# Extend.net
KiCad netlist of a schematic drawn in Altium Designer
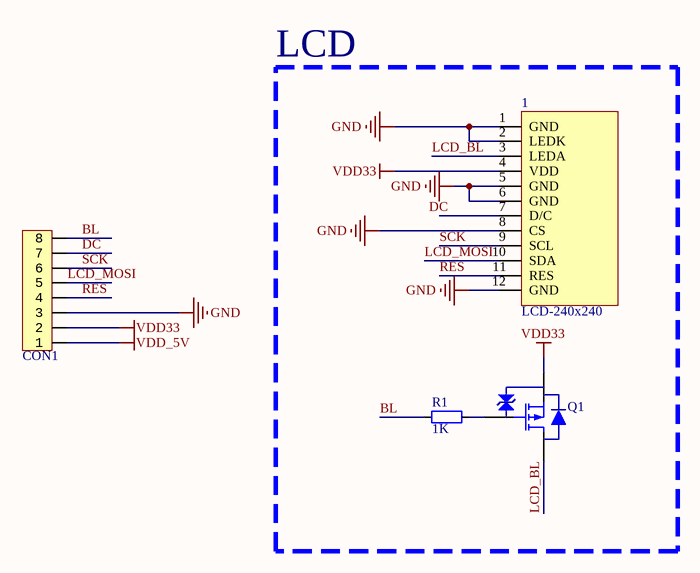
[diagram p0: Extend.SchDoc]

(export (version "E")
  (design (tool "Eeschema 10.0.6"))
  (components
    (comp (ref "1")
      (value "LCD-240x240")
      (footprint "LCD-240x240-NoHole")
      (description "显示屏")
      (libsource (lib "ExtendBoard") (part "LCD-240x240"))
    )
    (comp (ref "CON1")
      (value "FFC_0.5_8")
      (footprint "FFC_0.5_8")
      (description "FFC")
      (libsource (lib "ExtendBoard") (part "FFC_0.5_8"))
    )
    (comp (ref "Q1")
      (value "AO3415A")
      (footprint "SOT23-3")
      (description "MOSFET")
      (fields (field (name "PUBLISHER") "Altium Limited"))
      (libsource (lib "ExtendBoard") (part "AO3415A"))
    )
    (comp (ref "R1")
      (value "1K")
      (footprint "RES_0402")
      (description "Resistor")
      (libsource (lib "ExtendBoard") (part "电阻-0402"))
    )
  )
  (nets
    (net (code "1") (name "/BL") (class "Default")
      (node (ref "CON1") (pin "8") (pinfunction "8_8") (pintype "passive"))
      (node (ref "R1") (pin "1") (pinfunction "1_1") (pintype "passive"))
    )
    (net (code "2") (name "/DC") (class "Default")
      (node (ref "1") (pin "7") (pinfunction "D/C_7") (pintype "passive"))
      (node (ref "CON1") (pin "7") (pinfunction "7_7") (pintype "passive"))
    )
    (net (code "3") (name "/LCD_BL") (class "Default")
      (node (ref "1") (pin "3") (pinfunction "LEDA_3") (pintype "passive"))
      (node (ref "Q1") (pin "3") (pinfunction "D_3") (pintype "passive"))
    )
    (net (code "4") (name "/LCD_MOSI") (class "Default")
      (node (ref "1") (pin "10") (pinfunction "SDA_10") (pintype "passive"))
      (node (ref "CON1") (pin "5") (pinfunction "5_5") (pintype "passive"))
    )
    (net (code "5") (name "/RES") (class "Default")
      (node (ref "1") (pin "11") (pinfunction "RES_11") (pintype "passive"))
      (node (ref "CON1") (pin "4") (pinfunction "4_4") (pintype "passive"))
    )
    (net (code "6") (name "/SCK") (class "Default")
      (node (ref "1") (pin "9") (pinfunction "SCL_9") (pintype "passive"))
      (node (ref "CON1") (pin "6") (pinfunction "6_6") (pintype "passive"))
    )
    (net (code "7") (name "GND") (class "Default")
      (node (ref "1") (pin "1") (pinfunction "GND_1") (pintype "passive"))
      (node (ref "1") (pin "12") (pinfunction "GND_12") (pintype "passive"))
      (node (ref "1") (pin "2") (pinfunction "LEDK_2") (pintype "passive"))
      (node (ref "1") (pin "5") (pinfunction "GND_5") (pintype "passive"))
      (node (ref "1") (pin "6") (pinfunction "GND_6") (pintype "passive"))
      (node (ref "1") (pin "8") (pinfunction "CS_8") (pintype "passive"))
      (node (ref "CON1") (pin "3") (pinfunction "3_3") (pintype "passive"))
    )
    (net (code "8") (name "Net-(Q1-G)") (class "Default")
      (node (ref "Q1") (pin "1") (pinfunction "G_1") (pintype "passive"))
      (node (ref "R1") (pin "2") (pinfunction "2_2") (pintype "passive"))
    )
    (net (code "9") (name "VDD33") (class "Default")
      (node (ref "1") (pin "4") (pinfunction "VDD_4") (pintype "passive"))
      (node (ref "CON1") (pin "2") (pinfunction "2_2") (pintype "passive"))
      (node (ref "Q1") (pin "2") (pinfunction "S_2") (pintype "passive"))
    )
    (net (code "10") (name "VDD_5V") (class "Default")
      (node (ref "CON1") (pin "1") (pinfunction "1_1") (pintype "passive"))
    )
  )
)
